# step-up.net
KiCad netlist of a schematic drawn in Altium Designer
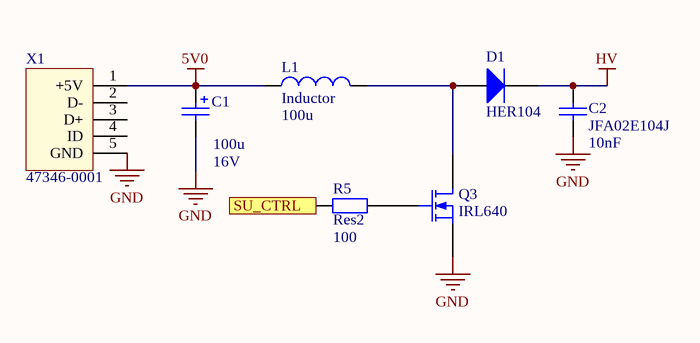
[diagram p0: step-up.SchDoc]

(export (version "E")
  (design (tool "Eeschema 10.0.6"))
  (components
    (comp (ref "C1")
      (value "100u")
      (footprint "cap_pol_5*11")
      (description "Polarized Capacitor (Axial)")
      (fields
        (field (name "VOLTAGE") "16V")
        (field (name "Comment") "Cap Pol2")
        (field (name "PUBLISHER") "Altium Limited")
      )
      (libsource (lib "Miscellaneous Devices") (part "Cap Pol2"))
    )
    (comp (ref "C2")
      (value "JFA02E104J")
      (footprint "film_cap_10")
      (description "Capacitor")
      (fields (field (name "ALTIUM_VALUE") "10nF") (field (name "PUBLISHER") "Altium Limited"))
      (libsource (lib "Miscellaneous Devices") (part "Cap"))
    )
    (comp (ref "D1")
      (value "HER104")
      (footprint "DO-204AL")
      (description "Default Diode")
      (fields (field (name "PUBLISHER") "Altium Limited"))
      (libsource (lib "Miscellaneous Devices") (part "Diode"))
    )
    (comp (ref "L1")
      (value "Inductor")
      (footprint "SDR0604")
      (fields (field (name "ALTIUM_VALUE") "100u") (field (name "PUBLISHER") "Altium Limited"))
      (libsource (lib "Miscellaneous Devices") (part "Inductor"))
    )
    (comp (ref "Q3")
      (value "IRL640")
      (footprint "to220_lying")
      (description "N-Channel MOSFET")
      (fields (field (name "PUBLISHER") "Altium Limited"))
      (libsource (lib "Miscellaneous Devices") (part "MOSFET-N"))
    )
    (comp (ref "R5")
      (value "Res2")
      (footprint "0402_res")
      (description "Resistor")
      (fields (field (name "ALTIUM_VALUE") "100") (field (name "PUBLISHER") "Altium Limited"))
      (libsource (lib "Miscellaneous Devices") (part "Res2"))
    )
    (comp (ref "X1")
      (value "47346-0001")
      (footprint "MOLEX_47346-0001")
      (libsource (lib "Schlib1") (part "micro_usb"))
    )
  )
  (nets
    (net (code "1") (name "/SU_CTRL") (class "Default")
      (node (ref "R5") (pin "1") (pinfunction "1_1") (pintype "passive"))
    )
    (net (code "2") (name "5V0") (class "Default")
      (node (ref "C1") (pin "1") (pinfunction "1_1") (pintype "passive"))
      (node (ref "L1") (pin "1") (pinfunction "1_1") (pintype "passive"))
      (node (ref "X1") (pin "1") (pinfunction "+5V_1") (pintype "passive"))
    )
    (net (code "3") (name "GND") (class "Default")
      (node (ref "C1") (pin "2") (pinfunction "2_2") (pintype "passive"))
      (node (ref "C2") (pin "1") (pinfunction "1_1") (pintype "passive"))
      (node (ref "Q3") (pin "3") (pinfunction "S_3") (pintype "passive"))
      (node (ref "X1") (pin "5") (pinfunction "GND_5") (pintype "passive"))
    )
    (net (code "4") (name "HV") (class "Default")
      (node (ref "C2") (pin "2") (pinfunction "2_2") (pintype "passive"))
      (node (ref "D1") (pin "2") (pinfunction "K_2") (pintype "passive"))
    )
    (net (code "5") (name "Net-(D1-A)") (class "Default")
      (node (ref "D1") (pin "1") (pinfunction "A_1") (pintype "passive"))
      (node (ref "L1") (pin "2") (pinfunction "2_2") (pintype "passive"))
      (node (ref "Q3") (pin "1") (pinfunction "D_1") (pintype "passive"))
    )
    (net (code "6") (name "Net-(Q3-G)") (class "Default")
      (node (ref "Q3") (pin "2") (pinfunction "G_2") (pintype "passive"))
      (node (ref "R5") (pin "2") (pinfunction "2_2") (pintype "passive"))
    )
    (net (code "7") (name "unconnected-(X1-D+-Pad3)") (class "Default")
      (node (ref "X1") (pin "3") (pinfunction "D+_3") (pintype "passive"))
    )
    (net (code "8") (name "unconnected-(X1-D--Pad2)") (class "Default")
      (node (ref "X1") (pin "2") (pinfunction "D-_2") (pintype "passive"))
    )
    (net (code "9") (name "unconnected-(X1-ID-Pad4)") (class "Default")
      (node (ref "X1") (pin "4") (pinfunction "ID_4") (pintype "passive"))
    )
  )
)
